# Temperature.net
KiCad netlist of a schematic drawn in EAGLE
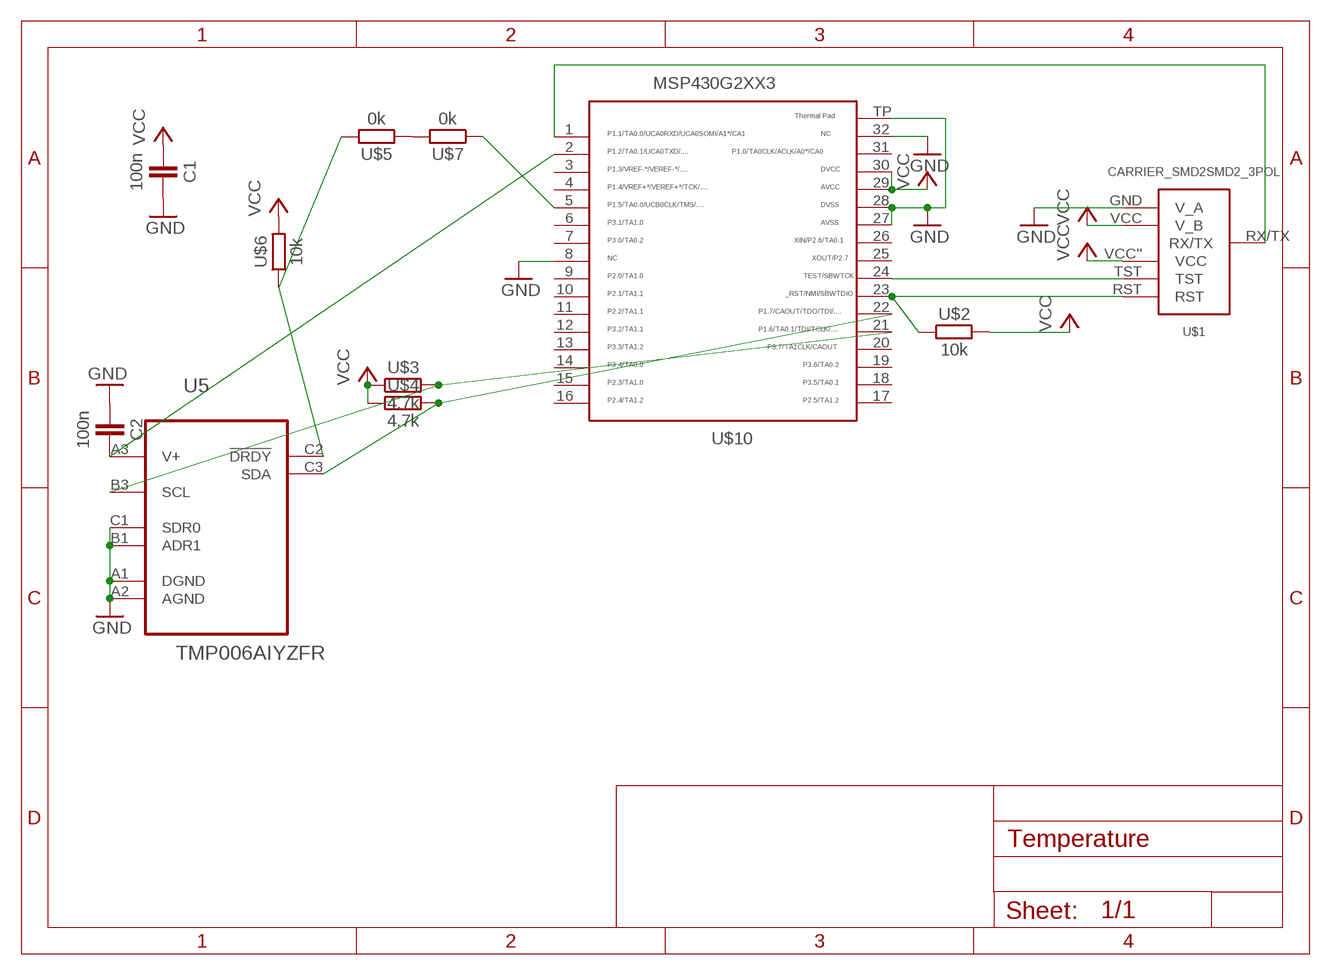
[diagram p0: schematic, sheet 1]

(export (version "E")
  (design (tool "Eeschema 10.0.6"))
  (components
    (comp (ref "C1")
      (value "100n")
      (footprint "eagle-import:603")
      (libsource (lib "eagle-import") (part "CAPACITOR"))
    )
    (comp (ref "C2")
      (value "100n")
      (footprint "eagle-import:603")
      (libsource (lib "eagle-import") (part "CAPACITOR"))
    )
    (comp (ref "U$1")
      (value "CARRIER_SMD2SMD2_3POL")
      (footprint "eagle-import:CARRIER_SMD2_3POL")
      (libsource (lib "eagle-import") (part "CARRIER_SMD2SMD2_3POL"))
    )
    (comp (ref "U$2")
      (value "10k")
      (footprint "eagle-import:603")
      (libsource (lib "eagle-import") (part "RESISTOR0603"))
    )
    (comp (ref "U$3")
      (value "4.7k")
      (footprint "eagle-import:603")
      (libsource (lib "eagle-import") (part "RESISTOR0603"))
    )
    (comp (ref "U$4")
      (value "4.7k")
      (footprint "eagle-import:603")
      (libsource (lib "eagle-import") (part "RESISTOR0603"))
    )
    (comp (ref "U$5")
      (value "0k")
      (footprint "eagle-import:603")
      (libsource (lib "eagle-import") (part "RESISTOR0603"))
    )
    (comp (ref "U$6")
      (value "10k")
      (footprint "eagle-import:603")
      (libsource (lib "eagle-import") (part "RESISTOR0603"))
    )
    (comp (ref "U$7")
      (value "0k")
      (footprint "eagle-import:603")
      (libsource (lib "eagle-import") (part "RESISTOR0603"))
    )
    (comp (ref "U$10")
      (value "MSP430G2553")
      (footprint "eagle-import:QFN32")
      (libsource (lib "eagle-import") (part "MSP430G2553"))
    )
    (comp (ref "U5")
      (value "TMP006AIYZFR")
      (footprint "eagle-import:BGA8C50P3X3_156X156X63")
      (fields (field (name "MPN") "TMP006AIYZFR "))
      (libsource (lib "eagle-import") (part "TMP006AIYZFR"))
    )
  )
  (nets
    (net (code "1") (name "GND") (class "Default")
      (node (ref "C1") (pin "2") (pinfunction "2_2") (pintype "passive"))
      (node (ref "C2") (pin "1") (pinfunction "1_1") (pintype "passive"))
      (node (ref "U$1") (pin "GND") (pinfunction "V_A_GND") (pintype "bidirectional"))
      (node (ref "U$10") (pin "27") (pinfunction "27_27") (pintype "bidirectional"))
      (node (ref "U$10") (pin "28") (pinfunction "28_28") (pintype "bidirectional"))
      (node (ref "U$10") (pin "32") (pinfunction "32_32") (pintype "bidirectional"))
      (node (ref "U$10") (pin "8") (pinfunction "8_8") (pintype "bidirectional"))
      (node (ref "U$10") (pin "TP") (pinfunction "TP_TP") (pintype "bidirectional"))
      (node (ref "U5") (pin "A1") (pinfunction "DGND_A1") (pintype "passive"))
      (node (ref "U5") (pin "A2") (pinfunction "AGND_A2") (pintype "passive"))
      (node (ref "U5") (pin "B1") (pinfunction "ADR1_B1") (pintype "input"))
      (node (ref "U5") (pin "C1") (pinfunction "SDR0_C1") (pintype "passive"))
    )
    (net (code "2") (name "Net-(U$1-PadRST)") (class "Default")
      (node (ref "U$1") (pin "RST") (pinfunction "RST_RST") (pintype "bidirectional"))
      (node (ref "U$10") (pin "23") (pinfunction "23_23") (pintype "bidirectional"))
      (node (ref "U$2") (pin "1") (pinfunction "1_1") (pintype "passive"))
    )
    (net (code "3") (name "Net-(U$1-PadRX{slash}TX)") (class "Default")
      (node (ref "U$1") (pin "RX/TX") (pinfunction "RX/TX_RX/TX") (pintype "bidirectional"))
      (node (ref "U$10") (pin "1") (pinfunction "1_1") (pintype "bidirectional"))
    )
    (net (code "4") (name "Net-(U$1-PadTST)") (class "Default")
      (node (ref "U$1") (pin "TST") (pinfunction "TST_TST") (pintype "bidirectional"))
      (node (ref "U$10") (pin "24") (pinfunction "24_24") (pintype "bidirectional"))
    )
    (net (code "5") (name "Net-(U$5-Pad1)") (class "Default")
      (node (ref "U$5") (pin "1") (pinfunction "1_1") (pintype "passive"))
      (node (ref "U$7") (pin "2") (pinfunction "2_2") (pintype "passive"))
    )
    (net (code "6") (name "Net-(U$10-Pad5)") (class "Default")
      (node (ref "U$10") (pin "5") (pinfunction "5_5") (pintype "bidirectional"))
      (node (ref "U$7") (pin "1") (pinfunction "1_1") (pintype "passive"))
    )
    (net (code "7") (name "Net-(U5-SCL)") (class "Default")
      (node (ref "U$10") (pin "21") (pinfunction "21_21") (pintype "bidirectional"))
      (node (ref "U$3") (pin "2") (pinfunction "2_2") (pintype "passive"))
      (node (ref "U5") (pin "B3") (pinfunction "SCL_B3") (pintype "input"))
    )
    (net (code "8") (name "Net-(U5-SDA)") (class "Default")
      (node (ref "U$10") (pin "22") (pinfunction "22_22") (pintype "bidirectional"))
      (node (ref "U$4") (pin "2") (pinfunction "2_2") (pintype "passive"))
      (node (ref "U5") (pin "C3") (pinfunction "SDA_C3") (pintype "bidirectional"))
    )
    (net (code "9") (name "Net-(U5-V+)") (class "Default")
      (node (ref "C2") (pin "2") (pinfunction "2_2") (pintype "passive"))
      (node (ref "U$10") (pin "2") (pinfunction "2_2") (pintype "bidirectional"))
      (node (ref "U5") (pin "A3") (pinfunction "V+_A3") (pintype "power_in"))
    )
    (net (code "10") (name "Net-(U5-~{DRDY})") (class "Default")
      (node (ref "U$5") (pin "2") (pinfunction "2_2") (pintype "passive"))
      (node (ref "U$6") (pin "1") (pinfunction "1_1") (pintype "passive"))
      (node (ref "U5") (pin "C2") (pinfunction "~{DRDY}_C2") (pintype "passive"))
    )
    (net (code "11") (name "VCC") (class "Default")
      (node (ref "C1") (pin "1") (pinfunction "1_1") (pintype "passive"))
      (node (ref "U$1") (pin "VCC") (pinfunction "V_B_VCC") (pintype "bidirectional"))
      (node (ref "U$1") (pin "VCC''") (pinfunction "VCC_VCC''") (pintype "bidirectional"))
      (node (ref "U$10") (pin "29") (pinfunction "29_29") (pintype "bidirectional"))
      (node (ref "U$10") (pin "30") (pinfunction "30_30") (pintype "bidirectional"))
      (node (ref "U$2") (pin "2") (pinfunction "2_2") (pintype "passive"))
      (node (ref "U$3") (pin "1") (pinfunction "1_1") (pintype "passive"))
      (node (ref "U$4") (pin "1") (pinfunction "1_1") (pintype "passive"))
      (node (ref "U$6") (pin "2") (pinfunction "2_2") (pintype "passive"))
    )
    (net (code "12") (name "unconnected-(U$10-Pad3)") (class "Default")
      (node (ref "U$10") (pin "3") (pinfunction "3_3") (pintype "bidirectional"))
    )
    (net (code "13") (name "unconnected-(U$10-Pad4)") (class "Default")
      (node (ref "U$10") (pin "4") (pinfunction "4_4") (pintype "bidirectional"))
    )
    (net (code "14") (name "unconnected-(U$10-Pad6)") (class "Default")
      (node (ref "U$10") (pin "6") (pinfunction "6_6") (pintype "bidirectional"))
    )
    (net (code "15") (name "unconnected-(U$10-Pad7)") (class "Default")
      (node (ref "U$10") (pin "7") (pinfunction "7_7") (pintype "bidirectional"))
    )
    (net (code "16") (name "unconnected-(U$10-Pad9)") (class "Default")
      (node (ref "U$10") (pin "9") (pinfunction "9_9") (pintype "bidirectional"))
    )
    (net (code "17") (name "unconnected-(U$10-Pad10)") (class "Default")
      (node (ref "U$10") (pin "10") (pinfunction "10_10") (pintype "bidirectional"))
    )
    (net (code "18") (name "unconnected-(U$10-Pad11)") (class "Default")
      (node (ref "U$10") (pin "11") (pinfunction "11_11") (pintype "bidirectional"))
    )
    (net (code "19") (name "unconnected-(U$10-Pad12)") (class "Default")
      (node (ref "U$10") (pin "12") (pinfunction "12_12") (pintype "bidirectional"))
    )
    (net (code "20") (name "unconnected-(U$10-Pad13)") (class "Default")
      (node (ref "U$10") (pin "13") (pinfunction "13_13") (pintype "bidirectional"))
    )
    (net (code "21") (name "unconnected-(U$10-Pad14)") (class "Default")
      (node (ref "U$10") (pin "14") (pinfunction "14_14") (pintype "bidirectional"))
    )
    (net (code "22") (name "unconnected-(U$10-Pad15)") (class "Default")
      (node (ref "U$10") (pin "15") (pinfunction "15_15") (pintype "bidirectional"))
    )
    (net (code "23") (name "unconnected-(U$10-Pad16)") (class "Default")
      (node (ref "U$10") (pin "16") (pinfunction "16_16") (pintype "bidirectional"))
    )
    (net (code "24") (name "unconnected-(U$10-Pad17)") (class "Default")
      (node (ref "U$10") (pin "17") (pinfunction "17_17") (pintype "bidirectional"))
    )
    (net (code "25") (name "unconnected-(U$10-Pad18)") (class "Default")
      (node (ref "U$10") (pin "18") (pinfunction "18_18") (pintype "bidirectional"))
    )
    (net (code "26") (name "unconnected-(U$10-Pad19)") (class "Default")
      (node (ref "U$10") (pin "19") (pinfunction "19_19") (pintype "bidirectional"))
    )
    (net (code "27") (name "unconnected-(U$10-Pad20)") (class "Default")
      (node (ref "U$10") (pin "20") (pinfunction "20_20") (pintype "bidirectional"))
    )
    (net (code "28") (name "unconnected-(U$10-Pad25)") (class "Default")
      (node (ref "U$10") (pin "25") (pinfunction "25_25") (pintype "bidirectional"))
    )
    (net (code "29") (name "unconnected-(U$10-Pad26)") (class "Default")
      (node (ref "U$10") (pin "26") (pinfunction "26_26") (pintype "bidirectional"))
    )
    (net (code "30") (name "unconnected-(U$10-Pad31)") (class "Default")
      (node (ref "U$10") (pin "31") (pinfunction "31_31") (pintype "bidirectional"))
    )
  )
)
